# monitor.net
KiCad netlist of a schematic drawn in EAGLE
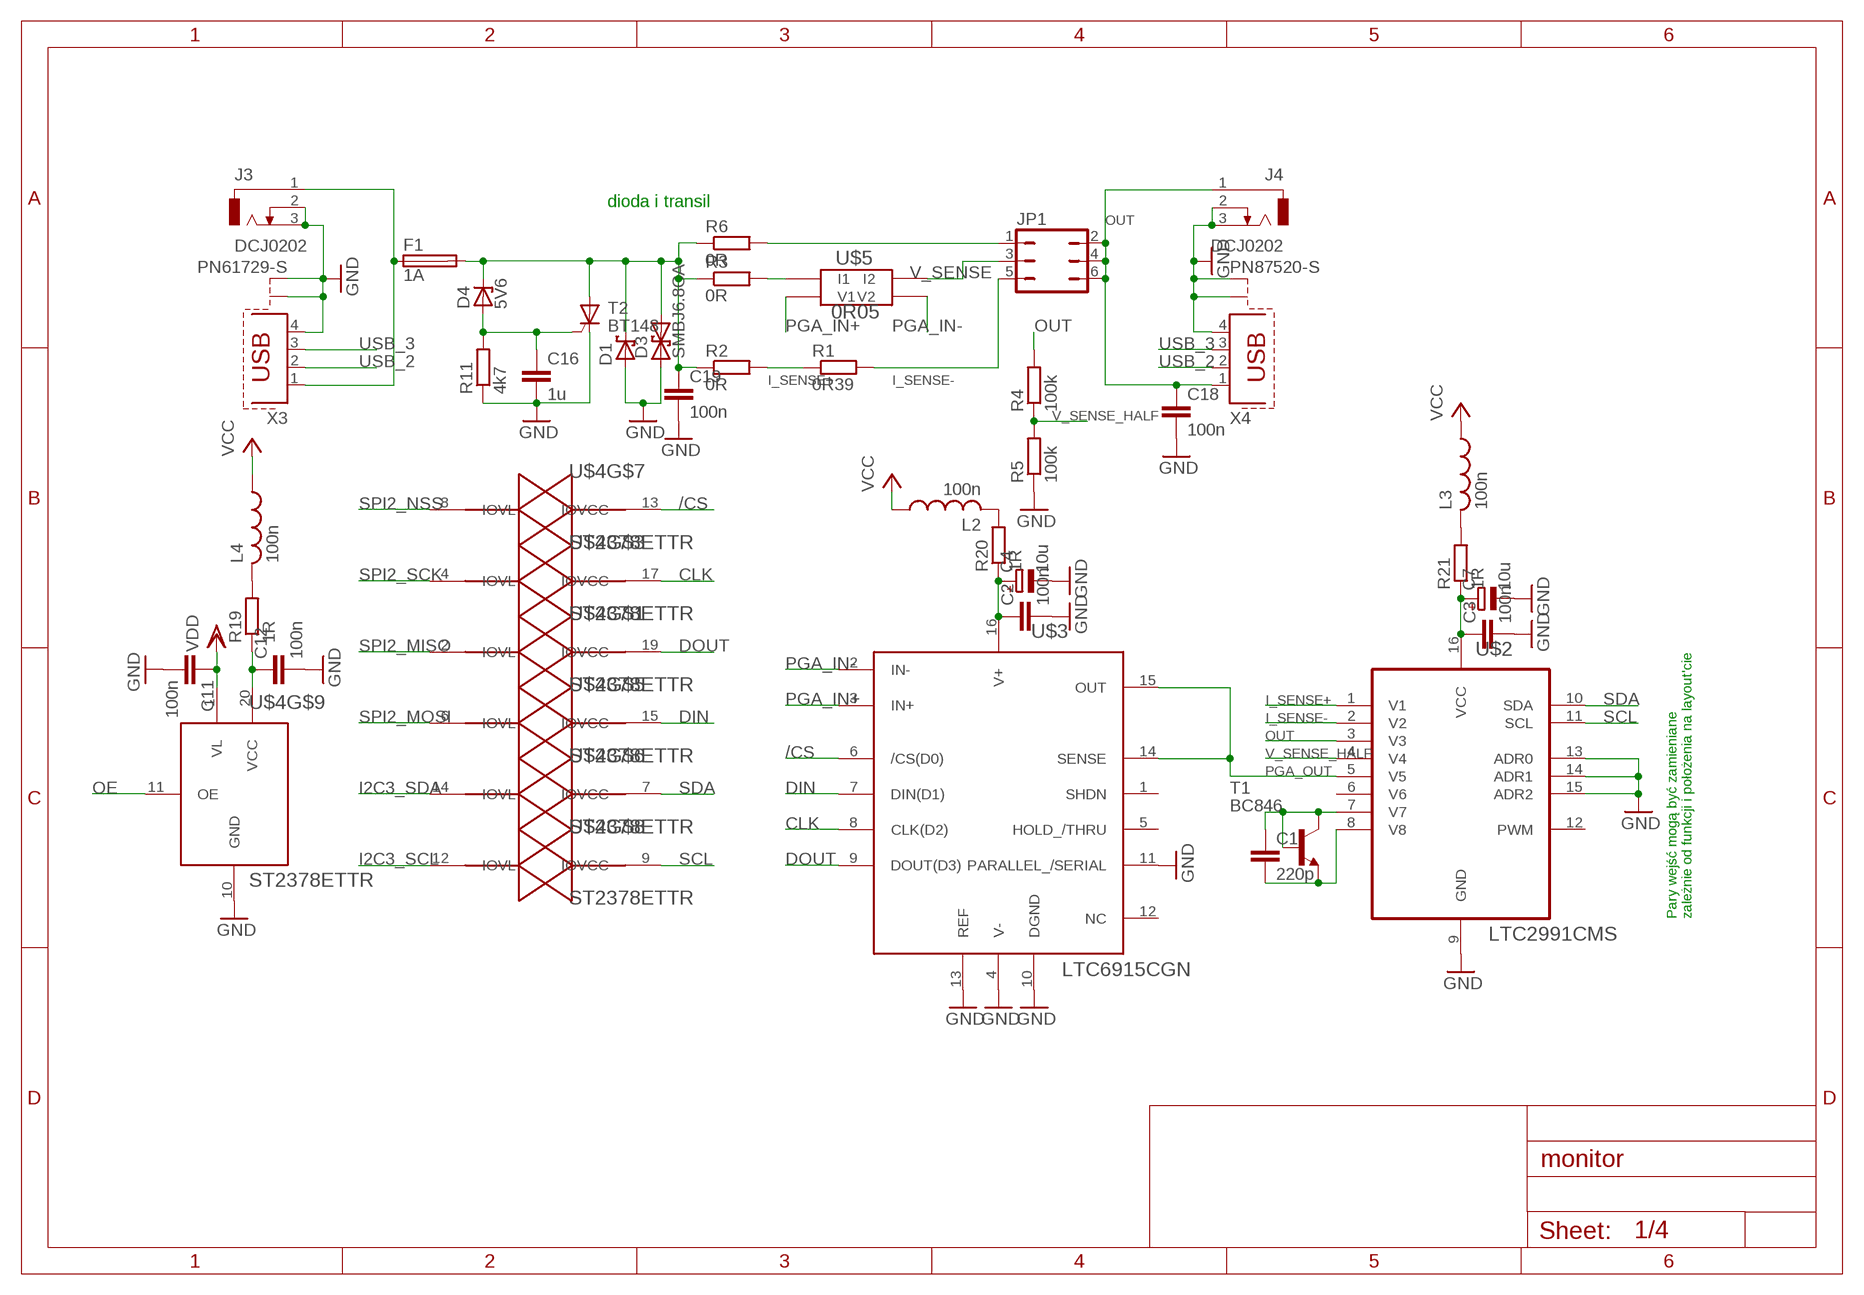
[diagram p0: schematic, sheet 1]
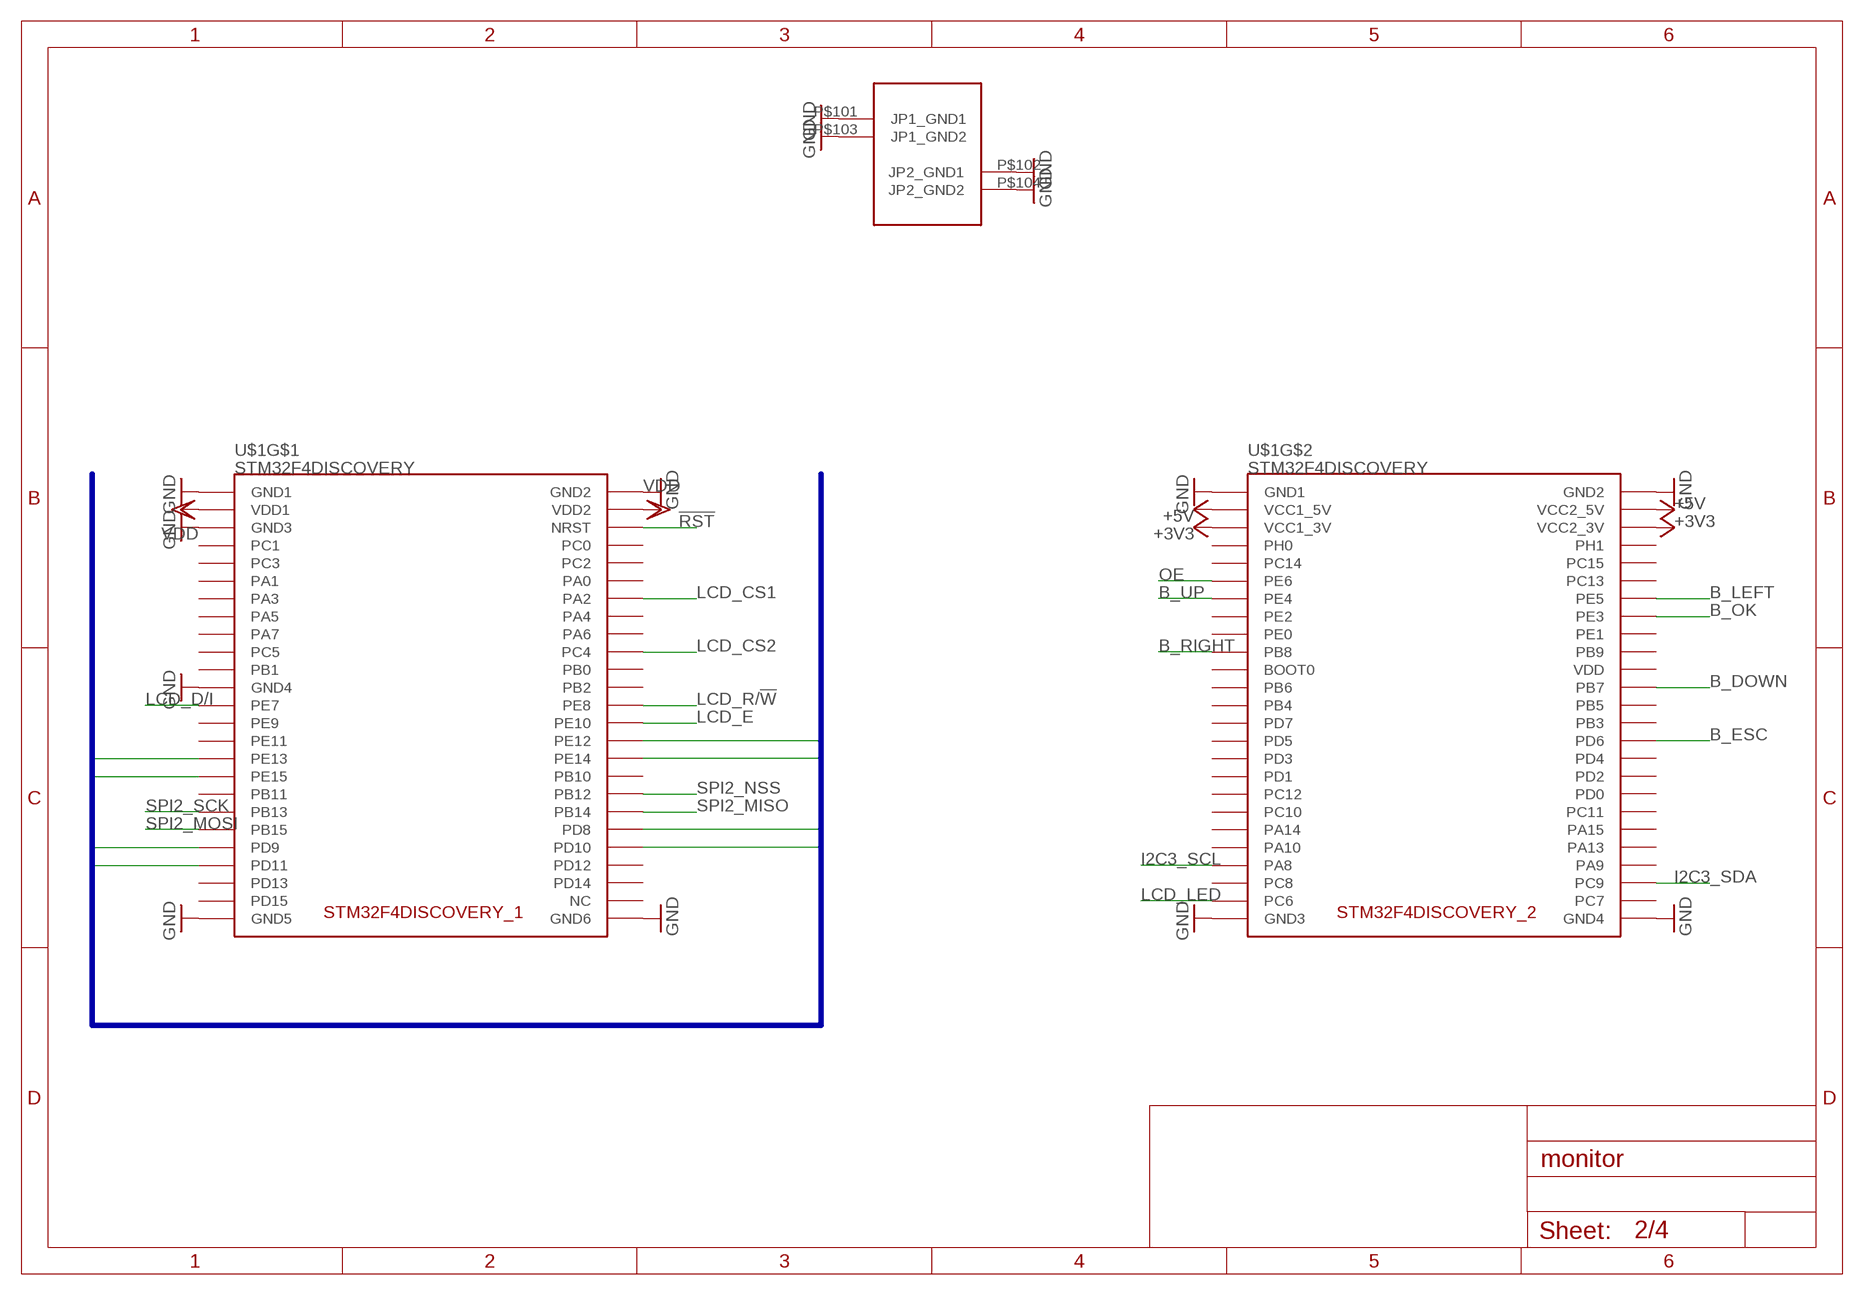
[diagram p1: schematic, sheet 2]
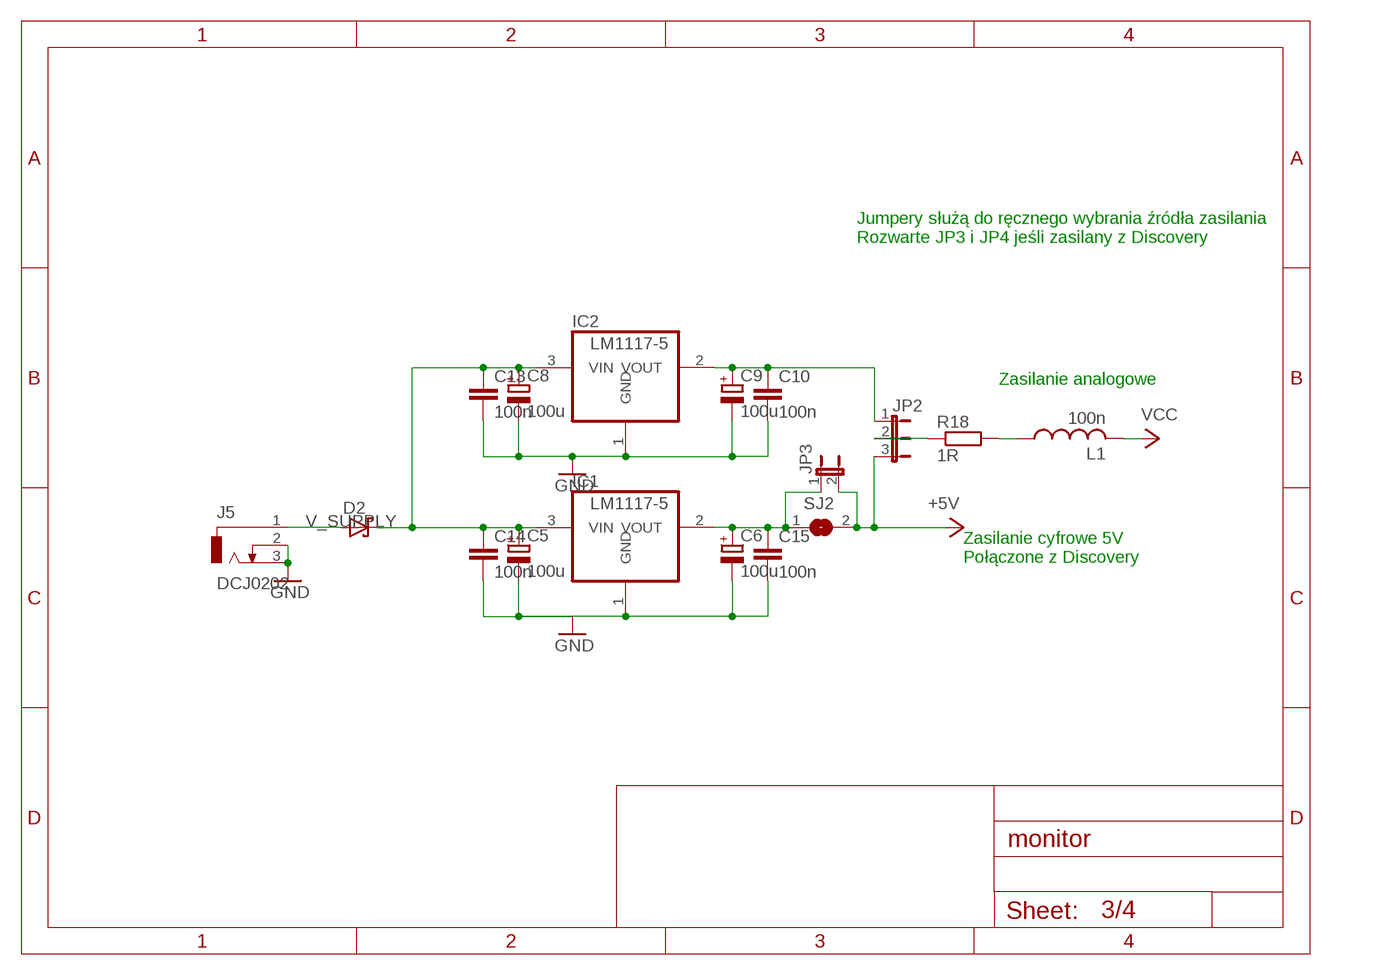
[diagram p2: schematic, sheet 3]
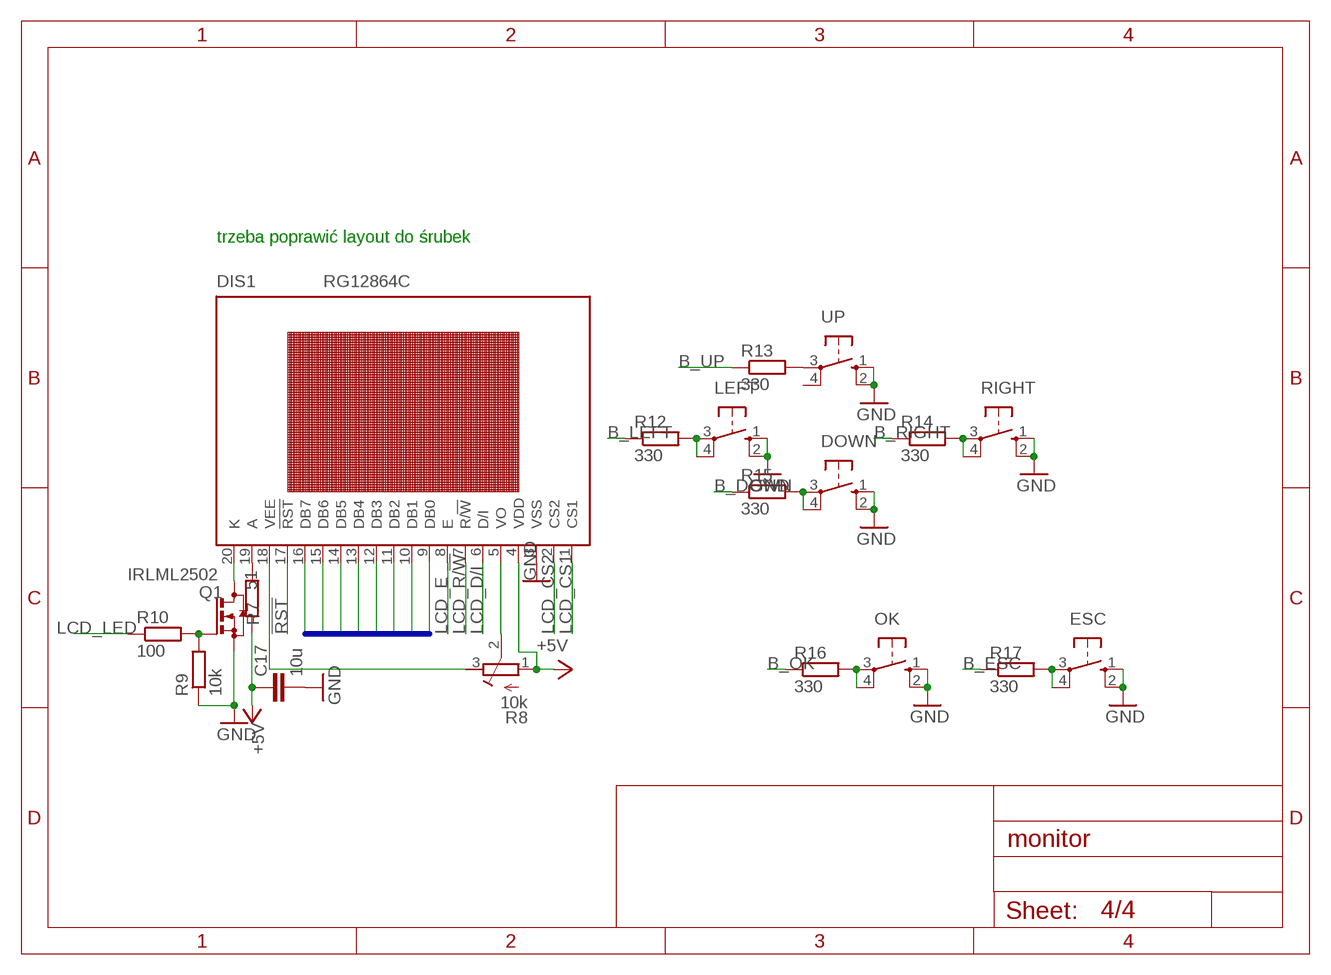
[diagram p3: schematic, sheet 4]

(export (version "E")
  (design (tool "Eeschema 10.0.6"))
  (components
    (comp (ref "C1")
      (value "220p")
      (footprint "eagle-import:C0805")
      (libsource (lib "eagle-import") (part "C-EUC0805"))
    )
    (comp (ref "C2")
      (value "100n")
      (footprint "eagle-import:C0603")
      (libsource (lib "eagle-import") (part "C-EUC0603"))
    )
    (comp (ref "C3")
      (value "100n")
      (footprint "eagle-import:C0603")
      (libsource (lib "eagle-import") (part "C-EUC0603"))
    )
    (comp (ref "C4")
      (value "10u")
      (footprint "eagle-import:SMC_A")
      (libsource (lib "eagle-import") (part "CPOL-EUSMCA"))
    )
    (comp (ref "C7")
      (value "10u")
      (footprint "eagle-import:SMC_A")
      (libsource (lib "eagle-import") (part "CPOL-EUSMCA"))
    )
    (comp (ref "C11")
      (value "100n")
      (footprint "eagle-import:C0603")
      (libsource (lib "eagle-import") (part "C-EUC0603"))
    )
    (comp (ref "C12")
      (value "100n")
      (footprint "eagle-import:C0603")
      (libsource (lib "eagle-import") (part "C-EUC0603"))
    )
    (comp (ref "C16")
      (value "1u")
      (footprint "eagle-import:C0805")
      (libsource (lib "eagle-import") (part "C-EUC0805"))
    )
    (comp (ref "C18")
      (value "100n")
      (footprint "eagle-import:C0603")
      (libsource (lib "eagle-import") (part "C-EUC0603"))
    )
    (comp (ref "C19")
      (value "100n")
      (footprint "eagle-import:C0603")
      (libsource (lib "eagle-import") (part "C-EUC0603"))
    )
    (comp (ref "D1")
      (value "SCHOTTKY-DIODESMD")
      (footprint "eagle-import:SMB")
      (libsource (lib "eagle-import") (part "SCHOTTKY-DIODESMD"))
    )
    (comp (ref "D3")
      (value "SMBJ6.8CA")
      (footprint "eagle-import:SMB")
      (libsource (lib "eagle-import") (part "SMBJ"))
    )
    (comp (ref "D4")
      (value "5V6")
      (footprint "eagle-import:SOD80C")
      (libsource (lib "eagle-import") (part "ZENER-DIODESOD80C"))
    )
    (comp (ref "F1")
      (value "1A")
      (footprint "eagle-import:R1206")
      (libsource (lib "eagle-import") (part "FUSE1206"))
    )
    (comp (ref "J3")
      (value "DCJ0202")
      (footprint "eagle-import:DCJ0202")
      (libsource (lib "eagle-import") (part "DCJ0202"))
    )
    (comp (ref "J4")
      (value "DCJ0202")
      (footprint "eagle-import:DCJ0202")
      (libsource (lib "eagle-import") (part "DCJ0202"))
    )
    (comp (ref "JP1")
      (value "JP3Q")
      (footprint "eagle-import:JP3Q")
      (libsource (lib "eagle-import") (part "JP3Q"))
    )
    (comp (ref "L2")
      (value "100n")
      (footprint "eagle-import:R0603")
      (libsource (lib "eagle-import") (part "L-US"))
    )
    (comp (ref "L3")
      (value "100n")
      (footprint "eagle-import:R0603")
      (libsource (lib "eagle-import") (part "L-US"))
    )
    (comp (ref "L4")
      (value "100n")
      (footprint "eagle-import:R0603")
      (libsource (lib "eagle-import") (part "L-US"))
    )
    (comp (ref "R1")
      (value "0R39")
      (footprint "eagle-import:0207_7")
      (libsource (lib "eagle-import") (part "resistor_R-EU_0207/7"))
    )
    (comp (ref "R2")
      (value "0R")
      (footprint "eagle-import:R0805")
      (libsource (lib "eagle-import") (part "R-EU_R0805"))
    )
    (comp (ref "R3")
      (value "0R")
      (footprint "eagle-import:R0805")
      (libsource (lib "eagle-import") (part "R-EU_R0805"))
    )
    (comp (ref "R4")
      (value "100k")
      (footprint "eagle-import:R0805")
      (libsource (lib "eagle-import") (part "R-EU_R0805"))
    )
    (comp (ref "R5")
      (value "100k")
      (footprint "eagle-import:R0805")
      (libsource (lib "eagle-import") (part "R-EU_R0805"))
    )
    (comp (ref "R6")
      (value "0R")
      (footprint "eagle-import:R0805")
      (libsource (lib "eagle-import") (part "R-EU_R0805"))
    )
    (comp (ref "R11")
      (value "4k7")
      (footprint "eagle-import:R0805")
      (libsource (lib "eagle-import") (part "R-EU_R0805"))
    )
    (comp (ref "R19")
      (value "1R")
      (footprint "eagle-import:R0603")
      (libsource (lib "eagle-import") (part "R-EU_R0603"))
    )
    (comp (ref "R20")
      (value "1R")
      (footprint "eagle-import:R0603")
      (libsource (lib "eagle-import") (part "R-EU_R0603"))
    )
    (comp (ref "R21")
      (value "1R")
      (footprint "eagle-import:R0603")
      (libsource (lib "eagle-import") (part "R-EU_R0603"))
    )
    (comp (ref "T1")
      (value "BC846")
      (footprint "eagle-import:SOT23")
      (libsource (lib "eagle-import") (part "BC846"))
    )
    (comp (ref "T2")
      (value "BT148")
      (footprint "eagle-import:SOT223")
      (libsource (lib "eagle-import") (part "BT148"))
    )
    (comp (ref "U$2")
      (value "LTC2991CMS")
      (footprint "eagle-import:SOP50P490X110-16N")
      (libsource (lib "eagle-import") (part "LTC2991CMS"))
    )
    (comp (ref "U$3")
      (value "LTC6915CGN")
      (footprint "eagle-import:SOP65P640X120-16N")
      (libsource (lib "eagle-import") (part "LTC6915CGN"))
    )
    (comp (ref "U$4")
      (value "ST2378ETTR")
      (footprint "eagle-import:TSSOP20")
      (libsource (lib "eagle-import") (part "ST2378ETTR"))
    )
    (comp (ref "U$5")
      (value "0R05")
      (footprint "eagle-import:LVK12")
      (libsource (lib "eagle-import") (part "LVK12R050DER"))
    )
    (comp (ref "X3")
      (value "PN61729-S")
      (footprint "eagle-import:PN61729-S")
      (libsource (lib "eagle-import") (part "PN61729-S"))
    )
    (comp (ref "X4")
      (value "PN87520-S")
      (footprint "eagle-import:PN87520-S")
      (libsource (lib "eagle-import") (part "PN87520-S"))
    )
    (comp (ref "U$1")
      (value "STM32F4DISCOVERY")
      (footprint "eagle-import:STM32F4DISCOVERY")
      (libsource (lib "eagle-import") (part "STM32F4DISCOVERY"))
    )
    (comp (ref "C17")
      (value "10u")
      (footprint "eagle-import:C1206")
      (libsource (lib "eagle-import") (part "C-EUC1206"))
    )
    (comp (ref "DIS1")
      (value "RG12864C")
      (footprint "eagle-import:RG12864C")
      (libsource (lib "eagle-import") (part "RG12864C"))
    )
    (comp (ref "DOWN")
      (value "40-XX")
      (footprint "eagle-import:B3F-40XX")
      (fields (field (name "MF") "OMRON COMPONENTS USA") (field (name "MPN") "B3F-4000"))
      (libsource (lib "eagle-import") (part "40-XX"))
    )
    (comp (ref "ESC")
      (value "40-XX")
      (footprint "eagle-import:B3F-40XX")
      (fields (field (name "MF") "OMRON COMPONENTS USA") (field (name "MPN") "B3F-4000"))
      (libsource (lib "eagle-import") (part "40-XX"))
    )
    (comp (ref "LEFT")
      (value "40-XX")
      (footprint "eagle-import:B3F-40XX")
      (fields (field (name "MF") "OMRON COMPONENTS USA") (field (name "MPN") "B3F-4000"))
      (libsource (lib "eagle-import") (part "40-XX"))
    )
    (comp (ref "OK")
      (value "40-XX")
      (footprint "eagle-import:B3F-40XX")
      (fields (field (name "MF") "OMRON COMPONENTS USA") (field (name "MPN") "B3F-4000"))
      (libsource (lib "eagle-import") (part "40-XX"))
    )
    (comp (ref "Q1")
      (value "IRLML2502")
      (footprint "eagle-import:SOT23")
      (libsource (lib "eagle-import") (part "BSS123"))
    )
    (comp (ref "R7")
      (value "51")
      (footprint "eagle-import:R1206")
      (libsource (lib "eagle-import") (part "R-EU_R1206"))
    )
    (comp (ref "R8")
      (value "10k")
      (footprint "eagle-import:RTRIMTS53YJ")
      (libsource (lib "eagle-import") (part "TS53YJ"))
    )
    (comp (ref "R9")
      (value "10k")
      (footprint "eagle-import:R0805")
      (libsource (lib "eagle-import") (part "R-EU_R0805"))
    )
    (comp (ref "R10")
      (value "100")
      (footprint "eagle-import:R0805")
      (libsource (lib "eagle-import") (part "R-EU_R0805"))
    )
    (comp (ref "R12")
      (value "330")
      (footprint "eagle-import:R0805")
      (libsource (lib "eagle-import") (part "R-EU_R0805"))
    )
    (comp (ref "R13")
      (value "330")
      (footprint "eagle-import:R0805")
      (libsource (lib "eagle-import") (part "R-EU_R0805"))
    )
    (comp (ref "R14")
      (value "330")
      (footprint "eagle-import:R0805")
      (libsource (lib "eagle-import") (part "R-EU_R0805"))
    )
    (comp (ref "R15")
      (value "330")
      (footprint "eagle-import:R0805")
      (libsource (lib "eagle-import") (part "R-EU_R0805"))
    )
    (comp (ref "R16")
      (value "330")
      (footprint "eagle-import:R0805")
      (libsource (lib "eagle-import") (part "R-EU_R0805"))
    )
    (comp (ref "R17")
      (value "330")
      (footprint "eagle-import:R0805")
      (libsource (lib "eagle-import") (part "R-EU_R0805"))
    )
    (comp (ref "RIGHT")
      (value "40-XX")
      (footprint "eagle-import:B3F-40XX")
      (fields (field (name "MF") "OMRON COMPONENTS USA") (field (name "MPN") "B3F-4000"))
      (libsource (lib "eagle-import") (part "40-XX"))
    )
    (comp (ref "UP")
      (value "40-XX")
      (footprint "eagle-import:B3F-40XX")
      (fields (field (name "MF") "OMRON COMPONENTS USA") (field (name "MPN") "B3F-4000"))
      (libsource (lib "eagle-import") (part "40-XX"))
    )
    (comp (ref "C5")
      (value "100u")
      (footprint "eagle-import:SMC_B")
      (libsource (lib "eagle-import") (part "CPOL-EUSMCB"))
    )
    (comp (ref "C6")
      (value "100u")
      (footprint "eagle-import:SMC_B")
      (libsource (lib "eagle-import") (part "CPOL-EUSMCB"))
    )
    (comp (ref "C8")
      (value "100u")
      (footprint "eagle-import:SMC_B")
      (libsource (lib "eagle-import") (part "CPOL-EUSMCB"))
    )
    (comp (ref "C9")
      (value "100u")
      (footprint "eagle-import:SMC_B")
      (libsource (lib "eagle-import") (part "CPOL-EUSMCB"))
    )
    (comp (ref "C10")
      (value "100n")
      (footprint "eagle-import:C0603")
      (libsource (lib "eagle-import") (part "C-EUC0603"))
    )
    (comp (ref "C13")
      (value "100n")
      (footprint "eagle-import:C0603")
      (libsource (lib "eagle-import") (part "C-EUC0603"))
    )
    (comp (ref "C14")
      (value "100n")
      (footprint "eagle-import:C0603")
      (libsource (lib "eagle-import") (part "C-EUC0603"))
    )
    (comp (ref "C15")
      (value "100n")
      (footprint "eagle-import:C0603")
      (libsource (lib "eagle-import") (part "C-EUC0603"))
    )
    (comp (ref "D2")
      (value "SCHOTTKY-DIODESMD")
      (footprint "eagle-import:SMB")
      (libsource (lib "eagle-import") (part "SCHOTTKY-DIODESMD"))
    )
    (comp (ref "IC1")
      (value "LM1117-5")
      (footprint "eagle-import:SOT223")
      (fields (field (name "MPN") "REG1117"))
      (libsource (lib "eagle-import") (part "REG1117"))
    )
    (comp (ref "IC2")
      (value "LM1117-5")
      (footprint "eagle-import:SOT223")
      (fields (field (name "MPN") "REG1117"))
      (libsource (lib "eagle-import") (part "REG1117"))
    )
    (comp (ref "J5")
      (value "DCJ0202")
      (footprint "eagle-import:DCJ0202")
      (libsource (lib "eagle-import") (part "DCJ0202"))
    )
    (comp (ref "JP2")
      (value "JP2E")
      (footprint "eagle-import:JP2")
      (libsource (lib "eagle-import") (part "JP2E"))
    )
    (comp (ref "JP3")
      (value "JP1E")
      (footprint "eagle-import:JP1")
      (libsource (lib "eagle-import") (part "JP1E"))
    )
    (comp (ref "L1")
      (value "100n")
      (footprint "eagle-import:R0603")
      (libsource (lib "eagle-import") (part "L-US"))
    )
    (comp (ref "R18")
      (value "1R")
      (footprint "eagle-import:R0603")
      (libsource (lib "eagle-import") (part "R-EU_R0603"))
    )
    (comp (ref "SJ2") (value "SJ") (footprint "eagle-import:SJ") (libsource (lib "eagle-import") (part "SJ")))
  )
  (nets
    (net (code "1") (name "+3V3") (class "Default")
      (node (ref "U$1") (pin "P$55") (pinfunction "VCC1_3V_P$55") (pintype "bidirectional"))
      (node (ref "U$1") (pin "P$56") (pinfunction "VCC2_3V_P$56") (pintype "bidirectional"))
    )
    (net (code "2") (name "+5V") (class "Default")
      (node (ref "C17") (pin "1") (pinfunction "1_1") (pintype "passive"))
      (node (ref "DIS1") (pin "4") (pinfunction "VDD_4") (pintype "power_in"))
      (node (ref "JP2") (pin "3") (pinfunction "3_3") (pintype "passive"))
      (node (ref "JP3") (pin "2") (pinfunction "2_2") (pintype "passive"))
      (node (ref "R7") (pin "1") (pinfunction "1_1") (pintype "passive"))
      (node (ref "R8") (pin "1") (pinfunction "A_1") (pintype "passive"))
      (node (ref "SJ2") (pin "2") (pinfunction "2_2") (pintype "passive"))
      (node (ref "U$1") (pin "P$53") (pinfunction "VCC1_5V_P$53") (pintype "bidirectional"))
      (node (ref "U$1") (pin "P$54") (pinfunction "VCC2_5V_P$54") (pintype "bidirectional"))
    )
    (net (code "3") (name "B_DOWN") (class "Default")
      (node (ref "R15") (pin "1") (pinfunction "1_1") (pintype "passive"))
      (node (ref "U$1") (pin "P$74") (pinfunction "PB7_P$74") (pintype "bidirectional"))
    )
    (net (code "4") (name "B_ESC") (class "Default")
      (node (ref "R17") (pin "1") (pinfunction "1_1") (pintype "passive"))
      (node (ref "U$1") (pin "P$80") (pinfunction "PD6_P$80") (pintype "bidirectional"))
    )
    (net (code "5") (name "B_LEFT") (class "Default")
      (node (ref "R12") (pin "1") (pinfunction "1_1") (pintype "passive"))
      (node (ref "U$1") (pin "P$64") (pinfunction "PE5_P$64") (pintype "bidirectional"))
    )
    (net (code "6") (name "B_OK") (class "Default")
      (node (ref "R16") (pin "1") (pinfunction "1_1") (pintype "passive"))
      (node (ref "U$1") (pin "P$66") (pinfunction "PE3_P$66") (pintype "bidirectional"))
    )
    (net (code "7") (name "B_RIGHT") (class "Default")
      (node (ref "R14") (pin "1") (pinfunction "1_1") (pintype "passive"))
      (node (ref "U$1") (pin "P$69") (pinfunction "PB8_P$69") (pintype "bidirectional"))
    )
    (net (code "8") (name "B_UP") (class "Default")
      (node (ref "R13") (pin "1") (pinfunction "1_1") (pintype "passive"))
      (node (ref "U$1") (pin "P$63") (pinfunction "PE4_P$63") (pintype "bidirectional"))
    )
    (net (code "9") (name "CLK") (class "Default")
      (node (ref "U$3") (pin "8") (pinfunction "CLK(D2)_8") (pintype "bidirectional"))
      (node (ref "U$4") (pin "17") (pinfunction "IOVCC_17") (pintype "bidirectional"))
    )
    (net (code "10") (name "DIN") (class "Default")
      (node (ref "U$3") (pin "7") (pinfunction "DIN(D1)_7") (pintype "bidirectional"))
      (node (ref "U$4") (pin "15") (pinfunction "IOVCC_15") (pintype "bidirectional"))
    )
    (net (code "11") (name "DOUT") (class "Default")
      (node (ref "U$3") (pin "9") (pinfunction "DOUT(D3)_9") (pintype "bidirectional"))
      (node (ref "U$4") (pin "19") (pinfunction "IOVCC_19") (pintype "bidirectional"))
    )
    (net (code "12") (name "GND") (class "Default")
      (node (ref "C10") (pin "2") (pinfunction "2_2") (pintype "passive"))
      (node (ref "C11") (pin "2") (pinfunction "2_2") (pintype "passive"))
      (node (ref "C12") (pin "2") (pinfunction "2_2") (pintype "passive"))
      (node (ref "C13") (pin "2") (pinfunction "2_2") (pintype "passive"))
      (node (ref "C14") (pin "2") (pinfunction "2_2") (pintype "passive"))
      (node (ref "C15") (pin "2") (pinfunction "2_2") (pintype "passive"))
      (node (ref "C16") (pin "2") (pinfunction "2_2") (pintype "passive"))
      (node (ref "C17") (pin "2") (pinfunction "2_2") (pintype "passive"))
      (node (ref "C18") (pin "2") (pinfunction "2_2") (pintype "passive"))
      (node (ref "C19") (pin "2") (pinfunction "2_2") (pintype "passive"))
      (node (ref "C2") (pin "2") (pinfunction "2_2") (pintype "passive"))
      (node (ref "C3") (pin "2") (pinfunction "2_2") (pintype "passive"))
      (node (ref "C4") (pin "-") (pinfunction "-_-") (pintype "passive"))
      (node (ref "C5") (pin "-") (pinfunction "-_-") (pintype "passive"))
      (node (ref "C6") (pin "-") (pinfunction "-_-") (pintype "passive"))
      (node (ref "C7") (pin "-") (pinfunction "-_-") (pintype "passive"))
      (node (ref "C8") (pin "-") (pinfunction "-_-") (pintype "passive"))
      (node (ref "C9") (pin "-") (pinfunction "-_-") (pintype "passive"))
      (node (ref "D1") (pin "A") (pinfunction "A_A") (pintype "passive"))
      (node (ref "D3") (pin "A") (pinfunction "1_A") (pintype "passive"))
      (node (ref "DIS1") (pin "3") (pinfunction "VSS_3") (pintype "power_in"))
      (node (ref "DOWN") (pin "1") (pinfunction "S_1") (pintype "passive"))
      (node (ref "DOWN") (pin "2") (pinfunction "S1_2") (pintype "passive"))
      (node (ref "ESC") (pin "1") (pinfunction "S_1") (pintype "passive"))
      (node (ref "ESC") (pin "2") (pinfunction "S1_2") (pintype "passive"))
      (node (ref "IC1") (pin "1") (pinfunction "GND_1") (pintype "power_in"))
      (node (ref "IC2") (pin "1") (pinfunction "GND_1") (pintype "power_in"))
      (node (ref "J3") (pin "2") (pinfunction "2_2") (pintype "passive"))
      (node (ref "J3") (pin "3") (pinfunction "3_3") (pintype "passive"))
      (node (ref "J4") (pin "2") (pinfunction "2_2") (pintype "passive"))
      (node (ref "J4") (pin "3") (pinfunction "3_3") (pintype "passive"))
      (node (ref "J5") (pin "2") (pinfunction "2_2") (pintype "passive"))
      (node (ref "J5") (pin "3") (pinfunction "3_3") (pintype "passive"))
      (node (ref "LEFT") (pin "1") (pinfunction "S_1") (pintype "passive"))
      (node (ref "LEFT") (pin "2") (pinfunction "S1_2") (pintype "passive"))
      (node (ref "OK") (pin "1") (pinfunction "S_1") (pintype "passive"))
      (node (ref "OK") (pin "2") (pinfunction "S1_2") (pintype "passive"))
      (node (ref "Q1") (pin "2") (pinfunction "S_2") (pintype "passive"))
      (node (ref "R11") (pin "1") (pinfunction "1_1") (pintype "passive"))
      (node (ref "R5") (pin "1") (pinfunction "1_1") (pintype "passive"))
      (node (ref "R9") (pin "1") (pinfunction "1_1") (pintype "passive"))
      (node (ref "RIGHT") (pin "1") (pinfunction "S_1") (pintype "passive"))
      (node (ref "RIGHT") (pin "2") (pinfunction "S1_2") (pintype "passive"))
      (node (ref "T2") (pin "1") (pinfunction "C_1") (pintype "passive"))
      (node (ref "U$1") (pin "P$1") (pinfunction "GND1_P$1") (pintype "bidirectional"))
      (node (ref "U$1") (pin "P$100") (pinfunction "GND4_P$100") (pintype "bidirectional"))
      (node (ref "U$1") (pin "P$101") (pinfunction "JP1_GND1_P$101") (pintype "power_in"))
      (node (ref "U$1") (pin "P$102") (pinfunction "JP2_GND1_P$102") (pintype "power_in"))
      (node (ref "U$1") (pin "P$103") (pinfunction "JP1_GND2_P$103") (pintype "power_in"))
      (node (ref "U$1") (pin "P$104") (pinfunction "JP2_GND2_P$104") (pintype "power_in"))
      (node (ref "U$1") (pin "P$2") (pinfunction "GND2_P$2") (pintype "bidirectional"))
      (node (ref "U$1") (pin "P$23") (pinfunction "GND4_P$23") (pintype "bidirectional"))
      (node (ref "U$1") (pin "P$49") (pinfunction "GND5_P$49") (pintype "bidirectional"))
      (node (ref "U$1") (pin "P$5") (pinfunction "GND3_P$5") (pintype "bidirectional"))
      (node (ref "U$1") (pin "P$50") (pinfunction "GND6_P$50") (pintype "bidirectional"))
      (node (ref "U$1") (pin "P$51") (pinfunction "GND1_P$51") (pintype "bidirectional"))
      (node (ref "U$1") (pin "P$52") (pinfunction "GND2_P$52") (pintype "bidirectional"))
      (node (ref "U$1") (pin "P$99") (pinfunction "GND3_P$99") (pintype "bidirectional"))
      (node (ref "U$2") (pin "13") (pinfunction "ADR0_13") (pintype "input"))
      (node (ref "U$2") (pin "14") (pinfunction "ADR1_14") (pintype "input"))
      (node (ref "U$2") (pin "15") (pinfunction "ADR2_15") (pintype "input"))
      (node (ref "U$2") (pin "9") (pinfunction "GND_9") (pintype "power_in"))
      (node (ref "U$3") (pin "10") (pinfunction "DGND_10") (pintype "power_in"))
      (node (ref "U$3") (pin "11") (pinfunction "PARALLEL_/SERIAL_11") (pintype "input"))
      (node (ref "U$3") (pin "13") (pinfunction "REF_13") (pintype "bidirectional"))
      (node (ref "U$3") (pin "4") (pinfunction "V-_4") (pintype "power_in"))
      (node (ref "U$4") (pin "10") (pinfunction "GND_10") (pintype "power_in"))
      (node (ref "UP") (pin "1") (pinfunction "S_1") (pintype "passive"))
      (node (ref "UP") (pin "2") (pinfunction "S1_2") (pintype "passive"))
      (node (ref "X3") (pin "4") (pinfunction "4_4") (pintype "passive"))
      (node (ref "X3") (pin "S1") (pinfunction "S1_S1") (pintype "passive"))
      (node (ref "X3") (pin "S2") (pinfunction "S2_S2") (pintype "passive"))
      (node (ref "X4") (pin "4") (pinfunction "4_4") (pintype "passive"))
      (node (ref "X4") (pin "S1") (pinfunction "S1_S1") (pintype "passive"))
      (node (ref "X4") (pin "S2") (pinfunction "S2_S2") (pintype "passive"))
    )
    (net (code "13") (name "I2C3_SCL") (class "Default")
      (node (ref "U$1") (pin "P$93") (pinfunction "PA8_P$93") (pintype "bidirectional"))
      (node (ref "U$4") (pin "12") (pinfunction "IOVL_12") (pintype "bidirectional"))
    )
    (net (code "14") (name "I2C3_SDA") (class "Default")
      (node (ref "U$1") (pin "P$96") (pinfunction "PC9_P$96") (pintype "bidirectional"))
      (node (ref "U$4") (pin "14") (pinfunction "IOVL_14") (pintype "bidirectional"))
    )
    (net (code "15") (name "I_SENSE+") (class "Default")
      (node (ref "R1") (pin "1") (pinfunction "1_1") (pintype "passive"))
      (node (ref "R2") (pin "2") (pinfunction "2_2") (pintype "passive"))
      (node (ref "U$2") (pin "1") (pinfunction "V1_1") (pintype "input"))
    )
    (net (code "16") (name "I_SENSE-") (class "Default")
      (node (ref "JP1") (pin "5") (pinfunction "5_5") (pintype "passive"))
      (node (ref "R1") (pin "2") (pinfunction "2_2") (pintype "passive"))
      (node (ref "U$2") (pin "2") (pinfunction "V2_2") (pintype "input"))
    )
    (net (code "17") (name "LCD_CS1") (class "Default")
      (node (ref "DIS1") (pin "1") (pinfunction "CS1_1") (pintype "bidirectional"))
      (node (ref "U$1") (pin "P$14") (pinfunction "PA2_P$14") (pintype "bidirectional"))
    )
    (net (code "18") (name "LCD_CS2") (class "Default")
      (node (ref "DIS1") (pin "2") (pinfunction "CS2_2") (pintype "bidirectional"))
      (node (ref "U$1") (pin "P$20") (pinfunction "PC4_P$20") (pintype "bidirectional"))
    )
    (net (code "19") (name "LCD_D0") (class "Default")
      (node (ref "DIS1") (pin "9") (pinfunction "DB0_9") (pintype "bidirectional"))
      (node (ref "U$1") (pin "P$30") (pinfunction "PE12_P$30") (pintype "bidirectional"))
    )
    (net (code "20") (name "LCD_D1") (class "Default")
      (node (ref "DIS1") (pin "10") (pinfunction "DB1_10") (pintype "bidirectional"))
      (node (ref "U$1") (pin "P$31") (pinfunction "PE13_P$31") (pintype "bidirectional"))
    )
    (net (code "21") (name "LCD_D2") (class "Default")
      (node (ref "DIS1") (pin "11") (pinfunction "DB2_11") (pintype "bidirectional"))
      (node (ref "U$1") (pin "P$32") (pinfunction "PE14_P$32") (pintype "bidirectional"))
    )
    (net (code "22") (name "LCD_D3") (class "Default")
      (node (ref "DIS1") (pin "12") (pinfunction "DB3_12") (pintype "bidirectional"))
      (node (ref "U$1") (pin "P$33") (pinfunction "PE15_P$33") (pintype "bidirectional"))
    )
    (net (code "23") (name "LCD_D4") (class "Default")
      (node (ref "DIS1") (pin "13") (pinfunction "DB4_13") (pintype "bidirectional"))
      (node (ref "U$1") (pin "P$40") (pinfunction "PD8_P$40") (pintype "bidirectional"))
    )
    (net (code "24") (name "LCD_D5") (class "Default")
      (node (ref "DIS1") (pin "14") (pinfunction "DB5_14") (pintype "bidirectional"))
      (node (ref "U$1") (pin "P$41") (pinfunction "PD9_P$41") (pintype "bidirectional"))
    )
    (net (code "25") (name "LCD_D6") (class "Default")
      (node (ref "DIS1") (pin "15") (pinfunction "DB6_15") (pintype "input"))
      (node (ref "U$1") (pin "P$42") (pinfunction "PD10_P$42") (pintype "bidirectional"))
    )
    (net (code "26") (name "LCD_D7") (class "Default")
      (node (ref "DIS1") (pin "16") (pinfunction "DB7_16") (pintype "input"))
      (node (ref "U$1") (pin "P$43") (pinfunction "PD11_P$43") (pintype "bidirectional"))
    )
    (net (code "27") (name "LCD_D{slash}I") (class "Default")
      (node (ref "DIS1") (pin "6") (pinfunction "D/I_6") (pintype "input"))
      (node (ref "U$1") (pin "P$25") (pinfunction "PE7_P$25") (pintype "bidirectional"))
    )
    (net (code "28") (name "LCD_E") (class "Default")
      (node (ref "DIS1") (pin "8") (pinfunction "E_8") (pintype "bidirectional"))
      (node (ref "U$1") (pin "P$28") (pinfunction "PE10_P$28") (pintype "bidirectional"))
    )
    (net (code "29") (name "LCD_LED") (class "Default")
      (node (ref "R10") (pin "1") (pinfunction "1_1") (pintype "passive"))
      (node (ref "U$1") (pin "P$97") (pinfunction "PC6_P$97") (pintype "bidirectional"))
    )
    (net (code "30") (name "LCD_R{slash}~{W}") (class "Default")
      (node (ref "DIS1") (pin "7") (pinfunction "R/~{W}_7") (pintype "bidirectional"))
      (node (ref "U$1") (pin "P$26") (pinfunction "PE8_P$26") (pintype "bidirectional"))
    )
    (net (code "31") (name "Net-(D2-PadA)") (class "Default")
      (node (ref "D2") (pin "A") (pinfunction "A_A") (pintype "passive"))
      (node (ref "J5") (pin "1") (pinfunction "1_1") (pintype "passive"))
    )
    (net (code "32") (name "Net-(D3-2)") (class "Default")
      (node (ref "C19") (pin "1") (pinfunction "1_1") (pintype "passive"))
      (node (ref "D1") (pin "C") (pinfunction "C_C") (pintype "passive"))
      (node (ref "D3") (pin "C") (pinfunction "2_C") (pintype "passive"))
      (node (ref "D4") (pin "C") (pinfunction "C_C") (pintype "passive"))
      (node (ref "F1") (pin "2") (pinfunction "2_2") (pintype "passive"))
      (node (ref "R2") (pin "1") (pinfunction "1_1") (pintype "passive"))
      (node (ref "R3") (pin "1") (pinfunction "1_1") (pintype "passive"))
      (node (ref "R6") (pin "1") (pinfunction "1_1") (pintype "passive"))
      (node (ref "T2") (pin "2") (pinfunction "A_2") (pintype "passive"))
    )
    (net (code "33") (name "Net-(DIS1-A)") (class "Default")
      (node (ref "DIS1") (pin "19") (pinfunction "A_19") (pintype "passive"))
      (node (ref "R7") (pin "2") (pinfunction "2_2") (pintype "passive"))
    )
    (net (code "34") (name "Net-(DIS1-K)") (class "Default")
      (node (ref "DIS1") (pin "20") (pinfunction "K_20") (pintype "passive"))
      (node (ref "Q1") (pin "3") (pinfunction "D_3") (pintype "passive"))
    )
    (net (code "35") (name "Net-(DIS1-VEE)") (class "Default")
      (node (ref "DIS1") (pin "18") (pinfunction "VEE_18") (pintype "output"))
      (node (ref "R8") (pin "3") (pinfunction "E_3") (pintype "passive"))
    )
    (net (code "36") (name "Net-(DIS1-VO)") (class "Default")
      (node (ref "DIS1") (pin "5") (pinfunction "VO_5") (pintype "passive"))
      (node (ref "R8") (pin "2") (pinfunction "S_2") (pintype "passive"))
    )
    (net (code "37") (name "Net-(DOWN-P)") (class "Default")
      (node (ref "DOWN") (pin "3") (pinfunction "P_3") (pintype "passive"))
      (node (ref "DOWN") (pin "4") (pinfunction "P1_4") (pintype "passive"))
      (node (ref "R15") (pin "2") (pinfunction "2_2") (pintype "passive"))
    )
    (net (code "38") (name "Net-(ESC-P)") (class "Default")
      (node (ref "ESC") (pin "3") (pinfunction "P_3") (pintype "passive"))
      (node (ref "ESC") (pin "4") (pinfunction "P1_4") (pintype "passive"))
      (node (ref "R17") (pin "2") (pinfunction "2_2") (pintype "passive"))
    )
    (net (code "39") (name "Net-(F1-Pad1)") (class "Default")
      (node (ref "F1") (pin "1") (pinfunction "1_1") (pintype "passive"))
      (node (ref "J3") (pin "1") (pinfunction "1_1") (pintype "passive"))
      (node (ref "X3") (pin "1") (pinfunction "1_1") (pintype "passive"))
    )
    (net (code "40") (name "Net-(IC1-VOUT)") (class "Default")
      (node (ref "C15") (pin "1") (pinfunction "1_1") (pintype "passive"))
      (node (ref "C6") (pin "+") (pinfunction "+_+") (pintype "passive"))
      (node (ref "IC1") (pin "2") (pinfunction "VOUT_2") (pintype "output"))
      (node (ref "JP3") (pin "1") (pinfunction "1_1") (pintype "passive"))
      (node (ref "SJ2") (pin "1") (pinfunction "1_1") (pintype "passive"))
    )
    (net (code "41") (name "Net-(IC2-VOUT)") (class "Default")
      (node (ref "C10") (pin "1") (pinfunction "1_1") (pintype "passive"))
      (node (ref "C9") (pin "+") (pinfunction "+_+") (pintype "passive"))
      (node (ref "IC2") (pin "2") (pinfunction "VOUT_2") (pintype "output"))
      (node (ref "JP2") (pin "1") (pinfunction "1_1") (pintype "passive"))
    )
    (net (code "42") (name "Net-(JP1-Pad1)") (class "Default")
      (node (ref "JP1") (pin "1") (pinfunction "1_1") (pintype "passive"))
      (node (ref "R6") (pin "2") (pinfunction "2_2") (pintype "passive"))
    )
    (net (code "43") (name "Net-(JP2-Pad2)") (class "Default")
      (node (ref "JP2") (pin "2") (pinfunction "2_2") (pintype "passive"))
      (node (ref "R18") (pin "1") (pinfunction "1_1") (pintype "passive"))
    )
    (net (code "44") (name "Net-(L1-Pad1)") (class "Default")
      (node (ref "L1") (pin "1") (pinfunction "1_1") (pintype "passive"))
      (node (ref "R18") (pin "2") (pinfunction "2_2") (pintype "passive"))
    )
    (net (code "45") (name "Net-(L2-Pad2)") (class "Default")
      (node (ref "L2") (pin "2") (pinfunction "2_2") (pintype "passive"))
      (node (ref "R20") (pin "2") (pinfunction "2_2") (pintype "passive"))
    )
    (net (code "46") (name "Net-(L3-Pad2)") (class "Default")
      (node (ref "L3") (pin "2") (pinfunction "2_2") (pintype "passive"))
      (node (ref "R21") (pin "2") (pinfunction "2_2") (pintype "passive"))
    )
    (net (code "47") (name "Net-(L4-Pad2)") (class "Default")
      (node (ref "L4") (pin "2") (pinfunction "2_2") (pintype "passive"))
      (node (ref "R19") (pin "2") (pinfunction "2_2") (pintype "passive"))
    )
    (net (code "48") (name "Net-(LEFT-P)") (class "Default")
      (node (ref "LEFT") (pin "3") (pinfunction "P_3") (pintype "passive"))
      (node (ref "LEFT") (pin "4") (pinfunction "P1_4") (pintype "passive"))
      (node (ref "R12") (pin "2") (pinfunction "2_2") (pintype "passive"))
    )
    (net (code "49") (name "Net-(OK-P)") (class "Default")
      (node (ref "OK") (pin "3") (pinfunction "P_3") (pintype "passive"))
      (node (ref "OK") (pin "4") (pinfunction "P1_4") (pintype "passive"))
      (node (ref "R16") (pin "2") (pinfunction "2_2") (pintype "passive"))
    )
    (net (code "50") (name "Net-(Q1-G)") (class "Default")
      (node (ref "Q1") (pin "1") (pinfunction "G_1") (pintype "passive"))
      (node (ref "R10") (pin "2") (pinfunction "2_2") (pintype "passive"))
      (node (ref "R9") (pin "2") (pinfunction "2_2") (pintype "passive"))
    )
    (net (code "51") (name "Net-(RIGHT-P)") (class "Default")
      (node (ref "R14") (pin "2") (pinfunction "2_2") (pintype "passive"))
      (node (ref "RIGHT") (pin "3") (pinfunction "P_3") (pintype "passive"))
      (node (ref "RIGHT") (pin "4") (pinfunction "P1_4") (pintype "passive"))
    )
    (net (code "52") (name "Net-(T1-B)") (class "Default")
      (node (ref "C1") (pin "1") (pinfunction "1_1") (pintype "passive"))
      (node (ref "T1") (pin "1") (pinfunction "B_1") (pintype "passive"))
      (node (ref "T1") (pin "3") (pinfunction "C_3") (pintype "passive"))
      (node (ref "U$2") (pin "7") (pinfunction "V7_7") (pintype "input"))
    )
    (net (code "53") (name "Net-(T1-E)") (class "Default")
      (node (ref "C1") (pin "2") (pinfunction "2_2") (pintype "passive"))
      (node (ref "T1") (pin "2") (pinfunction "E_2") (pintype "passive"))
      (node (ref "U$2") (pin "8") (pinfunction "V8_8") (pintype "input"))
    )
    (net (code "54") (name "Net-(T2-G)") (class "Default")
      (node (ref "C16") (pin "1") (pinfunction "1_1") (pintype "passive"))
      (node (ref "D4") (pin "A") (pinfunction "A_A") (pintype "passive"))
      (node (ref "R11") (pin "2") (pinfunction "2_2") (pintype "passive"))
      (node (ref "T2") (pin "3") (pinfunction "G_3") (pintype "passive"))
    )
    (net (code "55") (name "Net-(U$2-VCC)") (class "Default")
      (node (ref "C3") (pin "1") (pinfunction "1_1") (pintype "passive"))
      (node (ref "C7") (pin "+") (pinfunction "+_+") (pintype "passive"))
      (node (ref "R21") (pin "1") (pinfunction "1_1") (pintype "passive"))
      (node (ref "U$2") (pin "16") (pinfunction "VCC_16") (pintype "power_in"))
    )
    (net (code "56") (name "Net-(U$3-V+)") (class "Default")
      (node (ref "C2") (pin "1") (pinfunction "1_1") (pintype "passive"))
      (node (ref "C4") (pin "+") (pinfunction "+_+") (pintype "passive"))
      (node (ref "R20") (pin "1") (pinfunction "1_1") (pintype "passive"))
      (node (ref "U$3") (pin "16") (pinfunction "V+_16") (pintype "power_in"))
    )
    (net (code "57") (name "Net-(U$4I-VCC)") (class "Default")
      (node (ref "C12") (pin "1") (pinfunction "1_1") (pintype "passive"))
      (node (ref "R19") (pin "1") (pinfunction "1_1") (pintype "passive"))
      (node (ref "U$4") (pin "20") (pinfunction "VCC_20") (pintype "power_in"))
    )
    (net (code "58") (name "Net-(U$5-I1)") (class "Default")
      (node (ref "R3") (pin "2") (pinfunction "2_2") (pintype "passive"))
      (node (ref "U$5") (pin "P$3") (pinfunction "I1_P$3") (pintype "bidirectional"))
    )
    (net (code "59") (name "Net-(UP-P)") (class "Default")
      (node (ref "R13") (pin "2") (pinfunction "2_2") (pintype "passive"))
      (node (ref "UP") (pin "3") (pinfunction "P_3") (pintype "passive"))
    )
    (net (code "60") (name "OE") (class "Default")
      (node (ref "U$1") (pin "P$61") (pinfunction "PE6_P$61") (pintype "bidirectional"))
      (node (ref "U$4") (pin "11") (pinfunction "OE_11") (pintype "bidirectional"))
    )
    (net (code "61") (name "OUT") (class "Default")
      (node (ref "C18") (pin "1") (pinfunction "1_1") (pintype "passive"))
      (node (ref "J4") (pin "1") (pinfunction "1_1") (pintype "passive"))
      (node (ref "JP1") (pin "2") (pinfunction "2_2") (pintype "passive"))
      (node (ref "JP1") (pin "4") (pinfunction "4_4") (pintype "passive"))
      (node (ref "JP1") (pin "6") (pinfunction "6_6") (pintype "passive"))
      (node (ref "R4") (pin "2") (pinfunction "2_2") (pintype "passive"))
      (node (ref "U$2") (pin "3") (pinfunction "V3_3") (pintype "input"))
      (node (ref "X4") (pin "1") (pinfunction "1_1") (pintype "passive"))
    )
    (net (code "62") (name "PGA_IN+") (class "Default")
      (node (ref "U$3") (pin "3") (pinfunction "IN+_3") (pintype "input"))
      (node (ref "U$5") (pin "P$4") (pinfunction "V1_P$4") (pintype "bidirectional"))
    )
    (net (code "63") (name "PGA_IN-") (class "Default")
      (node (ref "U$3") (pin "2") (pinfunction "IN-_2") (pintype "input"))
      (node (ref "U$5") (pin "P$1") (pinfunction "V2_P$1") (pintype "bidirectional"))
    )
    (net (code "64") (name "PGA_OUT") (class "Default")
      (node (ref "U$2") (pin "5") (pinfunction "V5_5") (pintype "input"))
      (node (ref "U$3") (pin "14") (pinfunction "SENSE_14") (pintype "bidirectional"))
      (node (ref "U$3") (pin "15") (pinfunction "OUT_15") (pintype "output"))
    )
    (net (code "65") (name "SCL") (class "Default")
      (node (ref "U$2") (pin "11") (pinfunction "SCL_11") (pintype "input"))
      (node (ref "U$4") (pin "9") (pinfunction "IOVCC_9") (pintype "bidirectional"))
    )
    (net (code "66") (name "SDA") (class "Default")
      (node (ref "U$2") (pin "10") (pinfunction "SDA_10") (pintype "bidirectional"))
      (node (ref "U$4") (pin "7") (pinfunction "IOVCC_7") (pintype "bidirectional"))
    )
    (net (code "67") (name "SPI2_MISO") (class "Default")
      (node (ref "U$1") (pin "P$38") (pinfunction "PB14_P$38") (pintype "bidirectional"))
      (node (ref "U$4") (pin "2") (pinfunction "IOVL_2") (pintype "bidirectional"))
    )
    (net (code "68") (name "SPI2_MOSI") (class "Default")
      (node (ref "U$1") (pin "P$39") (pinfunction "PB15_P$39") (pintype "bidirectional"))
      (node (ref "U$4") (pin "6") (pinfunction "IOVL_6") (pintype "bidirectional"))
    )
    (net (code "69") (name "SPI2_NSS") (class "Default")
      (node (ref "U$1") (pin "P$36") (pinfunction "PB12_P$36") (pintype "bidirectional"))
      (node (ref "U$4") (pin "8") (pinfunction "IOVL_8") (pintype "bidirectional"))
    )
    (net (code "70") (name "SPI2_SCK") (class "Default")
      (node (ref "U$1") (pin "P$37") (pinfunction "PB13_P$37") (pintype "bidirectional"))
      (node (ref "U$4") (pin "4") (pinfunction "IOVL_4") (pintype "bidirectional"))
    )
    (net (code "71") (name "USB_2") (class "Default")
      (node (ref "X3") (pin "2") (pinfunction "2_2") (pintype "passive"))
      (node (ref "X4") (pin "2") (pinfunction "2_2") (pintype "passive"))
    )
    (net (code "72") (name "USB_3") (class "Default")
      (node (ref "X3") (pin "3") (pinfunction "3_3") (pintype "passive"))
      (node (ref "X4") (pin "3") (pinfunction "3_3") (pintype "passive"))
    )
    (net (code "73") (name "VCC") (class "Default")
      (node (ref "L1") (pin "2") (pinfunction "2_2") (pintype "passive"))
      (node (ref "L2") (pin "1") (pinfunction "1_1") (pintype "passive"))
      (node (ref "L3") (pin "1") (pinfunction "1_1") (pintype "passive"))
      (node (ref "L4") (pin "1") (pinfunction "1_1") (pintype "passive"))
    )
    (net (code "74") (name "VDD") (class "Default")
      (node (ref "C11") (pin "1") (pinfunction "1_1") (pintype "passive"))
      (node (ref "U$1") (pin "P$3") (pinfunction "VDD1_P$3") (pintype "bidirectional"))
      (node (ref "U$1") (pin "P$4") (pinfunction "VDD2_P$4") (pintype "bidirectional"))
      (node (ref "U$4") (pin "1") (pinfunction "VL_1") (pintype "power_in"))
    )
    (net (code "75") (name "V_SENSE") (class "Default")
      (node (ref "JP1") (pin "3") (pinfunction "3_3") (pintype "passive"))
      (node (ref "U$5") (pin "P$2") (pinfunction "I2_P$2") (pintype "bidirectional"))
    )
    (net (code "76") (name "V_SENSE_HALF") (class "Default")
      (node (ref "R4") (pin "1") (pinfunction "1_1") (pintype "passive"))
      (node (ref "R5") (pin "2") (pinfunction "2_2") (pintype "passive"))
      (node (ref "U$2") (pin "4") (pinfunction "V4_4") (pintype "input"))
    )
    (net (code "77") (name "V_SUPPLY") (class "Default")
      (node (ref "C13") (pin "1") (pinfunction "1_1") (pintype "passive"))
      (node (ref "C14") (pin "1") (pinfunction "1_1") (pintype "passive"))
      (node (ref "C5") (pin "+") (pinfunction "+_+") (pintype "passive"))
      (node (ref "C8") (pin "+") (pinfunction "+_+") (pintype "passive"))
      (node (ref "D2") (pin "C") (pinfunction "C_C") (pintype "passive"))
      (node (ref "IC1") (pin "3") (pinfunction "VIN_3") (pintype "input"))
      (node (ref "IC2") (pin "3") (pinfunction "VIN_3") (pintype "input"))
    )
    (net (code "78") (name "unconnected-(U$1A-NC-PadP$48)") (class "Default")
      (node (ref "U$1") (pin "P$48") (pinfunction "NC_P$48") (pintype "bidirectional"))
    )
    (net (code "79") (name "unconnected-(U$1A-PA0-PadP$12)") (class "Default")
      (node (ref "U$1") (pin "P$12") (pinfunction "PA0_P$12") (pintype "bidirectional"))
    )
    (net (code "80") (name "unconnected-(U$1A-PA1-PadP$11)") (class "Default")
      (node (ref "U$1") (pin "P$11") (pinfunction "PA1_P$11") (pintype "bidirectional"))
    )
    (net (code "81") (name "unconnected-(U$1A-PA3-PadP$13)") (class "Default")
      (node (ref "U$1") (pin "P$13") (pinfunction "PA3_P$13") (pintype "bidirectional"))
    )
    (net (code "82") (name "unconnected-(U$1A-PA4-PadP$16)") (class "Default")
      (node (ref "U$1") (pin "P$16") (pinfunction "PA4_P$16") (pintype "bidirectional"))
    )
    (net (code "83") (name "unconnected-(U$1A-PA5-PadP$15)") (class "Default")
      (node (ref "U$1") (pin "P$15") (pinfunction "PA5_P$15") (pintype "bidirectional"))
    )
    (net (code "84") (name "unconnected-(U$1A-PA6-PadP$18)") (class "Default")
      (node (ref "U$1") (pin "P$18") (pinfunction "PA6_P$18") (pintype "bidirectional"))
    )
    (net (code "85") (name "unconnected-(U$1A-PA7-PadP$17)") (class "Default")
      (node (ref "U$1") (pin "P$17") (pinfunction "PA7_P$17") (pintype "bidirectional"))
    )
    (net (code "86") (name "unconnected-(U$1A-PB0-PadP$22)") (class "Default")
      (node (ref "U$1") (pin "P$22") (pinfunction "PB0_P$22") (pintype "bidirectional"))
    )
    (net (code "87") (name "unconnected-(U$1A-PB1-PadP$21)") (class "Default")
      (node (ref "U$1") (pin "P$21") (pinfunction "PB1_P$21") (pintype "bidirectional"))
    )
    (net (code "88") (name "unconnected-(U$1A-PB2-PadP$24)") (class "Default")
      (node (ref "U$1") (pin "P$24") (pinfunction "PB2_P$24") (pintype "bidirectional"))
    )
    (net (code "89") (name "unconnected-(U$1A-PB10-PadP$34)") (class "Default")
      (node (ref "U$1") (pin "P$34") (pinfunction "PB10_P$34") (pintype "bidirectional"))
    )
    (net (code "90") (name "unconnected-(U$1A-PB11-PadP$35)") (class "Default")
      (node (ref "U$1") (pin "P$35") (pinfunction "PB11_P$35") (pintype "bidirectional"))
    )
    (net (code "91") (name "unconnected-(U$1A-PC0-PadP$8)") (class "Default")
      (node (ref "U$1") (pin "P$8") (pinfunction "PC0_P$8") (pintype "bidirectional"))
    )
    (net (code "92") (name "unconnected-(U$1A-PC1-PadP$7)") (class "Default")
      (node (ref "U$1") (pin "P$7") (pinfunction "PC1_P$7") (pintype "bidirectional"))
    )
    (net (code "93") (name "unconnected-(U$1A-PC2-PadP$10)") (class "Default")
      (node (ref "U$1") (pin "P$10") (pinfunction "PC2_P$10") (pintype "bidirectional"))
    )
    (net (code "94") (name "unconnected-(U$1A-PC3-PadP$9)") (class "Default")
      (node (ref "U$1") (pin "P$9") (pinfunction "PC3_P$9") (pintype "bidirectional"))
    )
    (net (code "95") (name "unconnected-(U$1A-PC5-PadP$19)") (class "Default")
      (node (ref "U$1") (pin "P$19") (pinfunction "PC5_P$19") (pintype "bidirectional"))
    )
    (net (code "96") (name "unconnected-(U$1A-PD12-PadP$44)") (class "Default")
      (node (ref "U$1") (pin "P$44") (pinfunction "PD12_P$44") (pintype "bidirectional"))
    )
    (net (code "97") (name "unconnected-(U$1A-PD13-PadP$45)") (class "Default")
      (node (ref "U$1") (pin "P$45") (pinfunction "PD13_P$45") (pintype "bidirectional"))
    )
    (net (code "98") (name "unconnected-(U$1A-PD14-PadP$46)") (class "Default")
      (node (ref "U$1") (pin "P$46") (pinfunction "PD14_P$46") (pintype "bidirectional"))
    )
    (net (code "99") (name "unconnected-(U$1A-PD15-PadP$47)") (class "Default")
      (node (ref "U$1") (pin "P$47") (pinfunction "PD15_P$47") (pintype "bidirectional"))
    )
    (net (code "100") (name "unconnected-(U$1A-PE9-PadP$27)") (class "Default")
      (node (ref "U$1") (pin "P$27") (pinfunction "PE9_P$27") (pintype "bidirectional"))
    )
    (net (code "101") (name "unconnected-(U$1A-PE11-PadP$29)") (class "Default")
      (node (ref "U$1") (pin "P$29") (pinfunction "PE11_P$29") (pintype "bidirectional"))
    )
    (net (code "102") (name "unconnected-(U$1B-BOOT0-PadP$71)") (class "Default")
      (node (ref "U$1") (pin "P$71") (pinfunction "BOOT0_P$71") (pintype "bidirectional"))
    )
    (net (code "103") (name "unconnected-(U$1B-PA9-PadP$94)") (class "Default")
      (node (ref "U$1") (pin "P$94") (pinfunction "PA9_P$94") (pintype "bidirectional"))
    )
    (net (code "104") (name "unconnected-(U$1B-PA10-PadP$91)") (class "Default")
      (node (ref "U$1") (pin "P$91") (pinfunction "PA10_P$91") (pintype "bidirectional"))
    )
    (net (code "105") (name "unconnected-(U$1B-PA13-PadP$92)") (class "Default")
      (node (ref "U$1") (pin "P$92") (pinfunction "PA13_P$92") (pintype "bidirectional"))
    )
    (net (code "106") (name "unconnected-(U$1B-PA14-PadP$89)") (class "Default")
      (node (ref "U$1") (pin "P$89") (pinfunction "PA14_P$89") (pintype "bidirectional"))
    )
    (net (code "107") (name "unconnected-(U$1B-PA15-PadP$90)") (class "Default")
      (node (ref "U$1") (pin "P$90") (pinfunction "PA15_P$90") (pintype "bidirectional"))
    )
    (net (code "108") (name "unconnected-(U$1B-PB3-PadP$78)") (class "Default")
      (node (ref "U$1") (pin "P$78") (pinfunction "PB3_P$78") (pintype "bidirectional"))
    )
    (net (code "109") (name "unconnected-(U$1B-PB4-PadP$75)") (class "Default")
      (node (ref "U$1") (pin "P$75") (pinfunction "PB4_P$75") (pintype "bidirectional"))
    )
    (net (code "110") (name "unconnected-(U$1B-PB5-PadP$76)") (class "Default")
      (node (ref "U$1") (pin "P$76") (pinfunction "PB5_P$76") (pintype "bidirectional"))
    )
    (net (code "111") (name "unconnected-(U$1B-PB6-PadP$73)") (class "Default")
      (node (ref "U$1") (pin "P$73") (pinfunction "PB6_P$73") (pintype "bidirectional"))
    )
    (net (code "112") (name "unconnected-(U$1B-PB9-PadP$70)") (class "Default")
      (node (ref "U$1") (pin "P$70") (pinfunction "PB9_P$70") (pintype "bidirectional"))
    )
    (net (code "113") (name "unconnected-(U$1B-PC7-PadP$98)") (class "Default")
      (node (ref "U$1") (pin "P$98") (pinfunction "PC7_P$98") (pintype "bidirectional"))
    )
    (net (code "114") (name "unconnected-(U$1B-PC8-PadP$95)") (class "Default")
      (node (ref "U$1") (pin "P$95") (pinfunction "PC8_P$95") (pintype "bidirectional"))
    )
    (net (code "115") (name "unconnected-(U$1B-PC10-PadP$87)") (class "Default")
      (node (ref "U$1") (pin "P$87") (pinfunction "PC10_P$87") (pintype "bidirectional"))
    )
    (net (code "116") (name "unconnected-(U$1B-PC11-PadP$88)") (class "Default")
      (node (ref "U$1") (pin "P$88") (pinfunction "PC11_P$88") (pintype "bidirectional"))
    )
    (net (code "117") (name "unconnected-(U$1B-PC12-PadP$85)") (class "Default")
      (node (ref "U$1") (pin "P$85") (pinfunction "PC12_P$85") (pintype "bidirectional"))
    )
    (net (code "118") (name "unconnected-(U$1B-PC13-PadP$62)") (class "Default")
      (node (ref "U$1") (pin "P$62") (pinfunction "PC13_P$62") (pintype "bidirectional"))
    )
    (net (code "119") (name "unconnected-(U$1B-PC14-PadP$59)") (class "Default")
      (node (ref "U$1") (pin "P$59") (pinfunction "PC14_P$59") (pintype "bidirectional"))
    )
    (net (code "120") (name "unconnected-(U$1B-PC15-PadP$60)") (class "Default")
      (node (ref "U$1") (pin "P$60") (pinfunction "PC15_P$60") (pintype "bidirectional"))
    )
    (net (code "121") (name "unconnected-(U$1B-PD0-PadP$86)") (class "Default")
      (node (ref "U$1") (pin "P$86") (pinfunction "PD0_P$86") (pintype "bidirectional"))
    )
    (net (code "122") (name "unconnected-(U$1B-PD1-PadP$83)") (class "Default")
      (node (ref "U$1") (pin "P$83") (pinfunction "PD1_P$83") (pintype "bidirectional"))
    )
    (net (code "123") (name "unconnected-(U$1B-PD2-PadP$84)") (class "Default")
      (node (ref "U$1") (pin "P$84") (pinfunction "PD2_P$84") (pintype "bidirectional"))
    )
    (net (code "124") (name "unconnected-(U$1B-PD3-PadP$81)") (class "Default")
      (node (ref "U$1") (pin "P$81") (pinfunction "PD3_P$81") (pintype "bidirectional"))
    )
    (net (code "125") (name "unconnected-(U$1B-PD4-PadP$82)") (class "Default")
      (node (ref "U$1") (pin "P$82") (pinfunction "PD4_P$82") (pintype "bidirectional"))
    )
    (net (code "126") (name "unconnected-(U$1B-PD5-PadP$79)") (class "Default")
      (node (ref "U$1") (pin "P$79") (pinfunction "PD5_P$79") (pintype "bidirectional"))
    )
    (net (code "127") (name "unconnected-(U$1B-PD7-PadP$77)") (class "Default")
      (node (ref "U$1") (pin "P$77") (pinfunction "PD7_P$77") (pintype "bidirectional"))
    )
    (net (code "128") (name "unconnected-(U$1B-PE0-PadP$67)") (class "Default")
      (node (ref "U$1") (pin "P$67") (pinfunction "PE0_P$67") (pintype "bidirectional"))
    )
    (net (code "129") (name "unconnected-(U$1B-PE1-PadP$68)") (class "Default")
      (node (ref "U$1") (pin "P$68") (pinfunction "PE1_P$68") (pintype "bidirectional"))
    )
    (net (code "130") (name "unconnected-(U$1B-PE2-PadP$65)") (class "Default")
      (node (ref "U$1") (pin "P$65") (pinfunction "PE2_P$65") (pintype "bidirectional"))
    )
    (net (code "131") (name "unconnected-(U$1B-PH0-PadP$57)") (class "Default")
      (node (ref "U$1") (pin "P$57") (pinfunction "PH0_P$57") (pintype "bidirectional"))
    )
    (net (code "132") (name "unconnected-(U$1B-PH1-PadP$58)") (class "Default")
      (node (ref "U$1") (pin "P$58") (pinfunction "PH1_P$58") (pintype "bidirectional"))
    )
    (net (code "133") (name "unconnected-(U$1B-VDD-PadP$72)") (class "Default")
      (node (ref "U$1") (pin "P$72") (pinfunction "VDD_P$72") (pintype "bidirectional"))
    )
    (net (code "134") (name "unconnected-(U$2-PWM-Pad12)") (class "Default")
      (node (ref "U$2") (pin "12") (pinfunction "PWM_12") (pintype "output"))
    )
    (net (code "135") (name "unconnected-(U$2-V6-Pad6)") (class "Default")
      (node (ref "U$2") (pin "6") (pinfunction "V6_6") (pintype "input"))
    )
    (net (code "136") (name "unconnected-(U$3-HOLD_{slash}THRU-Pad5)") (class "Default")
      (node (ref "U$3") (pin "5") (pinfunction "HOLD_/THRU_5") (pintype "bidirectional"))
    )
    (net (code "137") (name "unconnected-(U$3-NC-Pad12)") (class "Default")
      (node (ref "U$3") (pin "12") (pinfunction "NC_12") (pintype "no_connect"))
    )
    (net (code "138") (name "unconnected-(U$3-SHDN-Pad1)") (class "Default")
      (node (ref "U$3") (pin "1") (pinfunction "SHDN_1") (pintype "bidirectional"))
    )
    (net (code "139") (name "unconnected-(UP-P1-Pad4)") (class "Default")
      (node (ref "UP") (pin "4") (pinfunction "P1_4") (pintype "passive"))
    )
    (net (code "140") (name "{slash}CS") (class "Default")
      (node (ref "U$3") (pin "6") (pinfunction "/CS(D0)_6") (pintype "bidirectional"))
      (node (ref "U$4") (pin "13") (pinfunction "IOVCC_13") (pintype "bidirectional"))
    )
    (net (code "141") (name "~{RST}") (class "Default")
      (node (ref "DIS1") (pin "17") (pinfunction "~{RST}_17") (pintype "input"))
      (node (ref "U$1") (pin "P$6") (pinfunction "NRST_P$6") (pintype "bidirectional"))
    )
  )
)
